# Module_I2C_GPIO.net
KiCad netlist of a schematic drawn in EAGLE
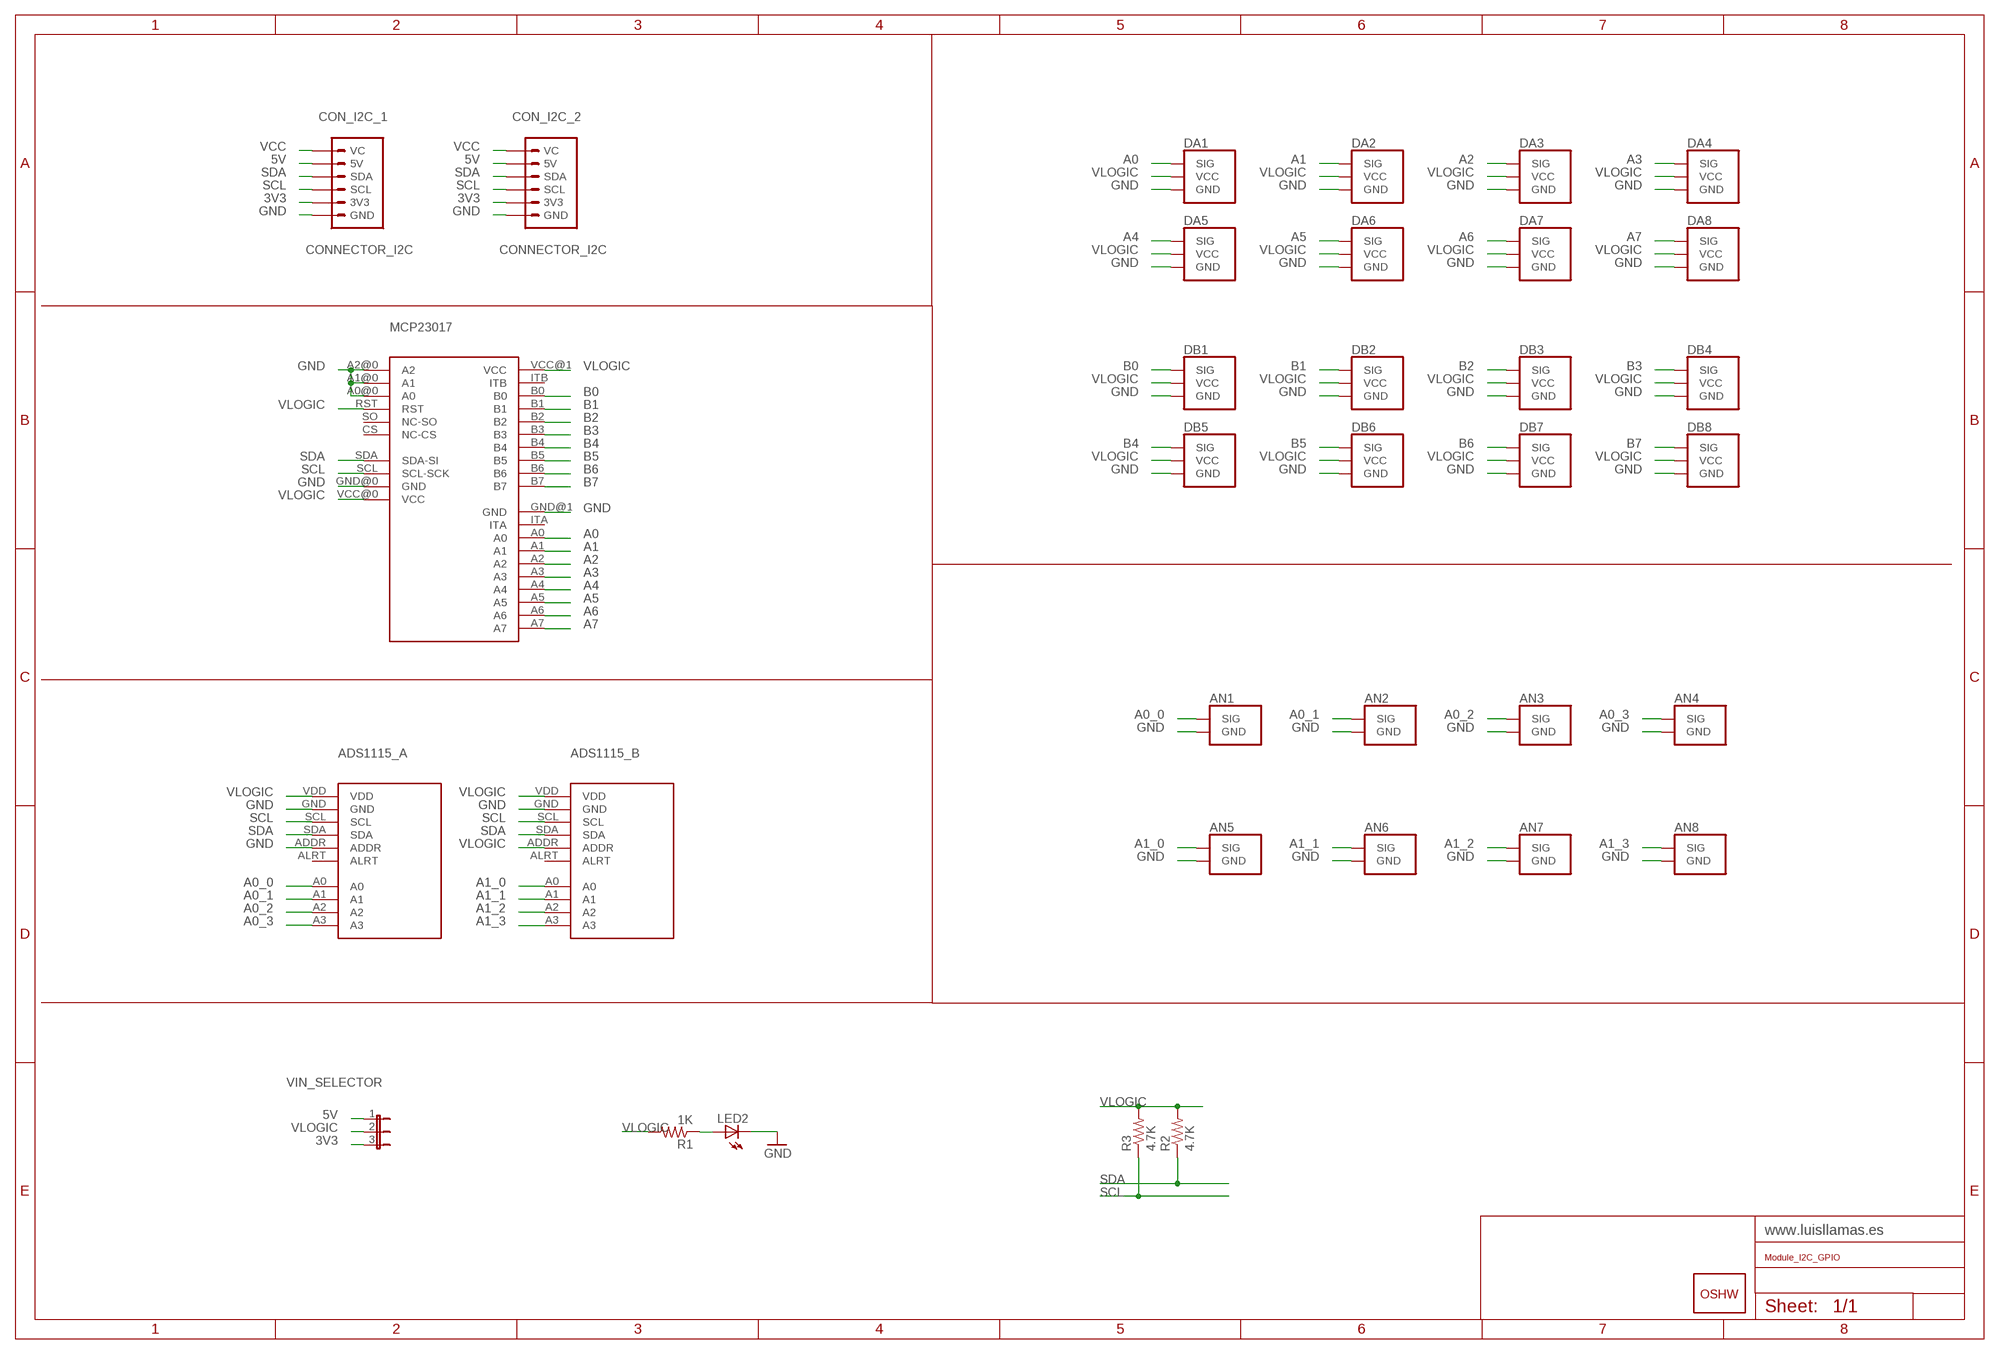
[diagram p0: schematic, sheet 1]

(export (version "E")
  (design (tool "Eeschema 10.0.6"))
  (components
    (comp (ref "ADS1115_A")
      (value "ADC-4CH-ADS1115")
      (footprint "eagle-import:ADC-4CH-ADS1115")
      (libsource (lib "eagle-import") (part "ADC-4CH-ADS1115"))
    )
    (comp (ref "ADS1115_B")
      (value "ADC-4CH-ADS1115")
      (footprint "eagle-import:ADC-4CH-ADS1115")
      (libsource (lib "eagle-import") (part "ADC-4CH-ADS1115"))
    )
    (comp (ref "AN1")
      (value "SERVO_2")
      (footprint "eagle-import:SERVO_2")
      (libsource (lib "eagle-import") (part "SERVO_2"))
    )
    (comp (ref "AN2")
      (value "SERVO_2")
      (footprint "eagle-import:SERVO_2")
      (libsource (lib "eagle-import") (part "SERVO_2"))
    )
    (comp (ref "AN3")
      (value "SERVO_2")
      (footprint "eagle-import:SERVO_2")
      (libsource (lib "eagle-import") (part "SERVO_2"))
    )
    (comp (ref "AN4")
      (value "SERVO_2")
      (footprint "eagle-import:SERVO_2")
      (libsource (lib "eagle-import") (part "SERVO_2"))
    )
    (comp (ref "AN5")
      (value "SERVO_2")
      (footprint "eagle-import:SERVO_2")
      (libsource (lib "eagle-import") (part "SERVO_2"))
    )
    (comp (ref "AN6")
      (value "SERVO_2")
      (footprint "eagle-import:SERVO_2")
      (libsource (lib "eagle-import") (part "SERVO_2"))
    )
    (comp (ref "AN7")
      (value "SERVO_2")
      (footprint "eagle-import:SERVO_2")
      (libsource (lib "eagle-import") (part "SERVO_2"))
    )
    (comp (ref "AN8")
      (value "SERVO_2")
      (footprint "eagle-import:SERVO_2")
      (libsource (lib "eagle-import") (part "SERVO_2"))
    )
    (comp (ref "CON_I2C_1")
      (value "CONNECTOR_I2C")
      (footprint "eagle-import:CONNECTOR_I2C")
      (libsource (lib "eagle-import") (part "CONNECTOR_I2C"))
    )
    (comp (ref "CON_I2C_2")
      (value "CONNECTOR_I2C")
      (footprint "eagle-import:CONNECTOR_I2C")
      (libsource (lib "eagle-import") (part "CONNECTOR_I2C"))
    )
    (comp (ref "DA1")
      (value "SERVOSERVO")
      (footprint "eagle-import:SERVO")
      (libsource (lib "eagle-import") (part "SERVOSERVO"))
    )
    (comp (ref "DA2")
      (value "SERVOSERVO")
      (footprint "eagle-import:SERVO")
      (libsource (lib "eagle-import") (part "SERVOSERVO"))
    )
    (comp (ref "DA3")
      (value "SERVOSERVO")
      (footprint "eagle-import:SERVO")
      (libsource (lib "eagle-import") (part "SERVOSERVO"))
    )
    (comp (ref "DA4")
      (value "SERVOSERVO")
      (footprint "eagle-import:SERVO")
      (libsource (lib "eagle-import") (part "SERVOSERVO"))
    )
    (comp (ref "DA5")
      (value "SERVOSERVO")
      (footprint "eagle-import:SERVO")
      (libsource (lib "eagle-import") (part "SERVOSERVO"))
    )
    (comp (ref "DA6")
      (value "SERVOSERVO")
      (footprint "eagle-import:SERVO")
      (libsource (lib "eagle-import") (part "SERVOSERVO"))
    )
    (comp (ref "DA7")
      (value "SERVOSERVO")
      (footprint "eagle-import:SERVO")
      (libsource (lib "eagle-import") (part "SERVOSERVO"))
    )
    (comp (ref "DA8")
      (value "SERVOSERVO")
      (footprint "eagle-import:SERVO")
      (libsource (lib "eagle-import") (part "SERVOSERVO"))
    )
    (comp (ref "DB1")
      (value "SERVOSERVO")
      (footprint "eagle-import:SERVO")
      (libsource (lib "eagle-import") (part "SERVOSERVO"))
    )
    (comp (ref "DB2")
      (value "SERVOSERVO")
      (footprint "eagle-import:SERVO")
      (libsource (lib "eagle-import") (part "SERVOSERVO"))
    )
    (comp (ref "DB3")
      (value "SERVOSERVO")
      (footprint "eagle-import:SERVO")
      (libsource (lib "eagle-import") (part "SERVOSERVO"))
    )
    (comp (ref "DB4")
      (value "SERVOSERVO")
      (footprint "eagle-import:SERVO")
      (libsource (lib "eagle-import") (part "SERVOSERVO"))
    )
    (comp (ref "DB5")
      (value "SERVOSERVO")
      (footprint "eagle-import:SERVO")
      (libsource (lib "eagle-import") (part "SERVOSERVO"))
    )
    (comp (ref "DB6")
      (value "SERVOSERVO")
      (footprint "eagle-import:SERVO")
      (libsource (lib "eagle-import") (part "SERVOSERVO"))
    )
    (comp (ref "DB7")
      (value "SERVOSERVO")
      (footprint "eagle-import:SERVO")
      (libsource (lib "eagle-import") (part "SERVOSERVO"))
    )
    (comp (ref "DB8")
      (value "SERVOSERVO")
      (footprint "eagle-import:SERVO")
      (libsource (lib "eagle-import") (part "SERVOSERVO"))
    )
    (comp (ref "GOLD_ORB_SM1")
      (value "OSHWLOGO_GOLD_ORB_MED")
      (footprint "eagle-import:OSHW1")
      (libsource (lib "eagle-import") (part "OSHWLOGO_GOLD_ORB_MED"))
    )
    (comp (ref "LED2")
      (value "LEDCHIP-LED0805")
      (footprint "eagle-import:CHIP-LED0805")
      (libsource (lib "eagle-import") (part "LEDCHIP-LED0805"))
    )
    (comp (ref "MCP23017")
      (value "GPIO-I2C-MCP23017")
      (footprint "eagle-import:GPIO-I2C-MCP23017")
      (libsource (lib "eagle-import") (part "GPIO-I2C-MCP23017"))
    )
    (comp (ref "R1")
      (value "1K")
      (footprint "eagle-import:R0805")
      (libsource (lib "eagle-import") (part "R-US_R0805"))
    )
    (comp (ref "R2")
      (value "4.7K")
      (footprint "eagle-import:R0805")
      (libsource (lib "eagle-import") (part "R-US_R0805"))
    )
    (comp (ref "R3")
      (value "4.7K")
      (footprint "eagle-import:R0805")
      (libsource (lib "eagle-import") (part "R-US_R0805"))
    )
    (comp (ref "VIN_SELECTOR")
      (value "JUMPER_3")
      (footprint "eagle-import:JUMPER_3")
      (libsource (lib "eagle-import") (part "JUMPER_3"))
    )
  )
  (nets
    (net (code "1") (name "/3V3") (class "Default")
      (node (ref "CON_I2C_1") (pin "3V3") (pinfunction "3V3_3V3") (pintype "passive"))
      (node (ref "CON_I2C_2") (pin "3V3") (pinfunction "3V3_3V3") (pintype "passive"))
      (node (ref "VIN_SELECTOR") (pin "3") (pinfunction "3_3") (pintype "passive"))
    )
    (net (code "2") (name "/5V") (class "Default")
      (node (ref "CON_I2C_1") (pin "5V") (pinfunction "5V_5V") (pintype "passive"))
      (node (ref "CON_I2C_2") (pin "5V") (pinfunction "5V_5V") (pintype "passive"))
      (node (ref "VIN_SELECTOR") (pin "1") (pinfunction "1_1") (pintype "passive"))
    )
    (net (code "3") (name "/A0") (class "Default")
      (node (ref "DA1") (pin "SIG") (pinfunction "SIG_SIG") (pintype "bidirectional"))
      (node (ref "MCP23017") (pin "A0") (pinfunction "A0_A0") (pintype "power_in"))
    )
    (net (code "4") (name "/A0_0") (class "Default")
      (node (ref "ADS1115_A") (pin "A0") (pinfunction "A0_A0") (pintype "input"))
      (node (ref "AN1") (pin "SIG") (pinfunction "SIG_SIG") (pintype "bidirectional"))
    )
    (net (code "5") (name "/A0_1") (class "Default")
      (node (ref "ADS1115_A") (pin "A1") (pinfunction "A1_A1") (pintype "input"))
      (node (ref "AN2") (pin "SIG") (pinfunction "SIG_SIG") (pintype "bidirectional"))
    )
    (net (code "6") (name "/A0_2") (class "Default")
      (node (ref "ADS1115_A") (pin "A2") (pinfunction "A2_A2") (pintype "input"))
      (node (ref "AN3") (pin "SIG") (pinfunction "SIG_SIG") (pintype "bidirectional"))
    )
    (net (code "7") (name "/A0_3") (class "Default")
      (node (ref "ADS1115_A") (pin "A3") (pinfunction "A3_A3") (pintype "input"))
      (node (ref "AN4") (pin "SIG") (pinfunction "SIG_SIG") (pintype "bidirectional"))
    )
    (net (code "8") (name "/A1") (class "Default")
      (node (ref "DA2") (pin "SIG") (pinfunction "SIG_SIG") (pintype "bidirectional"))
      (node (ref "MCP23017") (pin "A1") (pinfunction "A1_A1") (pintype "input"))
    )
    (net (code "9") (name "/A1_0") (class "Default")
      (node (ref "ADS1115_B") (pin "A0") (pinfunction "A0_A0") (pintype "input"))
      (node (ref "AN5") (pin "SIG") (pinfunction "SIG_SIG") (pintype "bidirectional"))
    )
    (net (code "10") (name "/A1_1") (class "Default")
      (node (ref "ADS1115_B") (pin "A1") (pinfunction "A1_A1") (pintype "input"))
      (node (ref "AN6") (pin "SIG") (pinfunction "SIG_SIG") (pintype "bidirectional"))
    )
    (net (code "11") (name "/A1_2") (class "Default")
      (node (ref "ADS1115_B") (pin "A2") (pinfunction "A2_A2") (pintype "input"))
      (node (ref "AN7") (pin "SIG") (pinfunction "SIG_SIG") (pintype "bidirectional"))
    )
    (net (code "12") (name "/A1_3") (class "Default")
      (node (ref "ADS1115_B") (pin "A3") (pinfunction "A3_A3") (pintype "input"))
      (node (ref "AN8") (pin "SIG") (pinfunction "SIG_SIG") (pintype "bidirectional"))
    )
    (net (code "13") (name "/A2") (class "Default")
      (node (ref "DA3") (pin "SIG") (pinfunction "SIG_SIG") (pintype "bidirectional"))
      (node (ref "MCP23017") (pin "A2") (pinfunction "A2_A2") (pintype "input"))
    )
    (net (code "14") (name "/A3") (class "Default")
      (node (ref "DA4") (pin "SIG") (pinfunction "SIG_SIG") (pintype "bidirectional"))
      (node (ref "MCP23017") (pin "A3") (pinfunction "A3_A3") (pintype "bidirectional"))
    )
    (net (code "15") (name "/A4") (class "Default")
      (node (ref "DA5") (pin "SIG") (pinfunction "SIG_SIG") (pintype "bidirectional"))
      (node (ref "MCP23017") (pin "A4") (pinfunction "A4_A4") (pintype "bidirectional"))
    )
    (net (code "16") (name "/A5") (class "Default")
      (node (ref "DA6") (pin "SIG") (pinfunction "SIG_SIG") (pintype "bidirectional"))
      (node (ref "MCP23017") (pin "A5") (pinfunction "A5_A5") (pintype "bidirectional"))
    )
    (net (code "17") (name "/A6") (class "Default")
      (node (ref "DA7") (pin "SIG") (pinfunction "SIG_SIG") (pintype "bidirectional"))
      (node (ref "MCP23017") (pin "A6") (pinfunction "A6_A6") (pintype "bidirectional"))
    )
    (net (code "18") (name "/A7") (class "Default")
      (node (ref "DA8") (pin "SIG") (pinfunction "SIG_SIG") (pintype "bidirectional"))
      (node (ref "MCP23017") (pin "A7") (pinfunction "A7_A7") (pintype "power_in"))
    )
    (net (code "19") (name "/B0") (class "Default")
      (node (ref "DB1") (pin "SIG") (pinfunction "SIG_SIG") (pintype "bidirectional"))
      (node (ref "MCP23017") (pin "B0") (pinfunction "B0_B0") (pintype "input"))
    )
    (net (code "20") (name "/B1") (class "Default")
      (node (ref "DB2") (pin "SIG") (pinfunction "SIG_SIG") (pintype "bidirectional"))
      (node (ref "MCP23017") (pin "B1") (pinfunction "B1_B1") (pintype "input"))
    )
    (net (code "21") (name "/B2") (class "Default")
      (node (ref "DB3") (pin "SIG") (pinfunction "SIG_SIG") (pintype "bidirectional"))
      (node (ref "MCP23017") (pin "B2") (pinfunction "B2_B2") (pintype "bidirectional"))
    )
    (net (code "22") (name "/B3") (class "Default")
      (node (ref "DB4") (pin "SIG") (pinfunction "SIG_SIG") (pintype "bidirectional"))
      (node (ref "MCP23017") (pin "B3") (pinfunction "B3_B3") (pintype "bidirectional"))
    )
    (net (code "23") (name "/B4") (class "Default")
      (node (ref "DB5") (pin "SIG") (pinfunction "SIG_SIG") (pintype "bidirectional"))
      (node (ref "MCP23017") (pin "B4") (pinfunction "B4_B4") (pintype "bidirectional"))
    )
    (net (code "24") (name "/B5") (class "Default")
      (node (ref "DB6") (pin "SIG") (pinfunction "SIG_SIG") (pintype "bidirectional"))
      (node (ref "MCP23017") (pin "B5") (pinfunction "B5_B5") (pintype "bidirectional"))
    )
    (net (code "25") (name "/B6") (class "Default")
      (node (ref "DB7") (pin "SIG") (pinfunction "SIG_SIG") (pintype "bidirectional"))
      (node (ref "MCP23017") (pin "B6") (pinfunction "B6_B6") (pintype "power_in"))
    )
    (net (code "26") (name "/B7") (class "Default")
      (node (ref "DB8") (pin "SIG") (pinfunction "SIG_SIG") (pintype "bidirectional"))
      (node (ref "MCP23017") (pin "B7") (pinfunction "B7_B7") (pintype "power_in"))
    )
    (net (code "27") (name "/SCL") (class "Default")
      (node (ref "ADS1115_A") (pin "SCL") (pinfunction "SCL_SCL") (pintype "bidirectional"))
      (node (ref "ADS1115_B") (pin "SCL") (pinfunction "SCL_SCL") (pintype "bidirectional"))
      (node (ref "CON_I2C_1") (pin "SCL") (pinfunction "SCL_SCL") (pintype "passive"))
      (node (ref "CON_I2C_2") (pin "SCL") (pinfunction "SCL_SCL") (pintype "passive"))
      (node (ref "MCP23017") (pin "SCL") (pinfunction "SCL-SCK_SCL") (pintype "input"))
      (node (ref "R3") (pin "1") (pinfunction "1_1") (pintype "passive"))
    )
    (net (code "28") (name "/SDA") (class "Default")
      (node (ref "ADS1115_A") (pin "SDA") (pinfunction "SDA_SDA") (pintype "bidirectional"))
      (node (ref "ADS1115_B") (pin "SDA") (pinfunction "SDA_SDA") (pintype "bidirectional"))
      (node (ref "CON_I2C_1") (pin "SDA") (pinfunction "SDA_SDA") (pintype "passive"))
      (node (ref "CON_I2C_2") (pin "SDA") (pinfunction "SDA_SDA") (pintype "passive"))
      (node (ref "MCP23017") (pin "SDA") (pinfunction "SDA-SI_SDA") (pintype "input"))
      (node (ref "R2") (pin "1") (pinfunction "1_1") (pintype "passive"))
    )
    (net (code "29") (name "/VCC") (class "Default")
      (node (ref "CON_I2C_1") (pin "VC") (pinfunction "VC_VC") (pintype "passive"))
      (node (ref "CON_I2C_2") (pin "VC") (pinfunction "VC_VC") (pintype "passive"))
    )
    (net (code "30") (name "/VLOGIC") (class "Default")
      (node (ref "ADS1115_A") (pin "VDD") (pinfunction "VDD_VDD") (pintype "power_in"))
      (node (ref "ADS1115_B") (pin "ADDR") (pinfunction "ADDR_ADDR") (pintype "bidirectional"))
      (node (ref "ADS1115_B") (pin "VDD") (pinfunction "VDD_VDD") (pintype "power_in"))
      (node (ref "DA1") (pin "VCC") (pinfunction "VCC_VCC") (pintype "power_in"))
      (node (ref "DA2") (pin "VCC") (pinfunction "VCC_VCC") (pintype "power_in"))
      (node (ref "DA3") (pin "VCC") (pinfunction "VCC_VCC") (pintype "power_in"))
      (node (ref "DA4") (pin "VCC") (pinfunction "VCC_VCC") (pintype "power_in"))
      (node (ref "DA5") (pin "VCC") (pinfunction "VCC_VCC") (pintype "power_in"))
      (node (ref "DA6") (pin "VCC") (pinfunction "VCC_VCC") (pintype "power_in"))
      (node (ref "DA7") (pin "VCC") (pinfunction "VCC_VCC") (pintype "power_in"))
      (node (ref "DA8") (pin "VCC") (pinfunction "VCC_VCC") (pintype "power_in"))
      (node (ref "DB1") (pin "VCC") (pinfunction "VCC_VCC") (pintype "power_in"))
      (node (ref "DB2") (pin "VCC") (pinfunction "VCC_VCC") (pintype "power_in"))
      (node (ref "DB3") (pin "VCC") (pinfunction "VCC_VCC") (pintype "power_in"))
      (node (ref "DB4") (pin "VCC") (pinfunction "VCC_VCC") (pintype "power_in"))
      (node (ref "DB5") (pin "VCC") (pinfunction "VCC_VCC") (pintype "power_in"))
      (node (ref "DB6") (pin "VCC") (pinfunction "VCC_VCC") (pintype "power_in"))
      (node (ref "DB7") (pin "VCC") (pinfunction "VCC_VCC") (pintype "power_in"))
      (node (ref "DB8") (pin "VCC") (pinfunction "VCC_VCC") (pintype "power_in"))
      (node (ref "MCP23017") (pin "RST") (pinfunction "RST_RST") (pintype "bidirectional"))
      (node (ref "MCP23017") (pin "VCC@0") (pinfunction "VCC_VCC@0") (pintype "input"))
      (node (ref "MCP23017") (pin "VCC@1") (pinfunction "VCC_VCC@1") (pintype "input"))
      (node (ref "R1") (pin "2") (pinfunction "2_2") (pintype "passive"))
      (node (ref "R2") (pin "2") (pinfunction "2_2") (pintype "passive"))
      (node (ref "R3") (pin "2") (pinfunction "2_2") (pintype "passive"))
      (node (ref "VIN_SELECTOR") (pin "2") (pinfunction "2_2") (pintype "passive"))
    )
    (net (code "31") (name "GND") (class "Default")
      (node (ref "ADS1115_A") (pin "ADDR") (pinfunction "ADDR_ADDR") (pintype "bidirectional"))
      (node (ref "ADS1115_A") (pin "GND") (pinfunction "GND_GND") (pintype "power_in"))
      (node (ref "ADS1115_B") (pin "GND") (pinfunction "GND_GND") (pintype "power_in"))
      (node (ref "AN1") (pin "GND") (pinfunction "GND_GND") (pintype "power_in"))
      (node (ref "AN2") (pin "GND") (pinfunction "GND_GND") (pintype "power_in"))
      (node (ref "AN3") (pin "GND") (pinfunction "GND_GND") (pintype "power_in"))
      (node (ref "AN4") (pin "GND") (pinfunction "GND_GND") (pintype "power_in"))
      (node (ref "AN5") (pin "GND") (pinfunction "GND_GND") (pintype "power_in"))
      (node (ref "AN6") (pin "GND") (pinfunction "GND_GND") (pintype "power_in"))
      (node (ref "AN7") (pin "GND") (pinfunction "GND_GND") (pintype "power_in"))
      (node (ref "AN8") (pin "GND") (pinfunction "GND_GND") (pintype "power_in"))
      (node (ref "CON_I2C_1") (pin "GND") (pinfunction "GND_GND") (pintype "passive"))
      (node (ref "CON_I2C_2") (pin "GND") (pinfunction "GND_GND") (pintype "passive"))
      (node (ref "DA1") (pin "GND") (pinfunction "GND_GND") (pintype "power_in"))
      (node (ref "DA2") (pin "GND") (pinfunction "GND_GND") (pintype "power_in"))
      (node (ref "DA3") (pin "GND") (pinfunction "GND_GND") (pintype "power_in"))
      (node (ref "DA4") (pin "GND") (pinfunction "GND_GND") (pintype "power_in"))
      (node (ref "DA5") (pin "GND") (pinfunction "GND_GND") (pintype "power_in"))
      (node (ref "DA6") (pin "GND") (pinfunction "GND_GND") (pintype "power_in"))
      (node (ref "DA7") (pin "GND") (pinfunction "GND_GND") (pintype "power_in"))
      (node (ref "DA8") (pin "GND") (pinfunction "GND_GND") (pintype "power_in"))
      (node (ref "DB1") (pin "GND") (pinfunction "GND_GND") (pintype "power_in"))
      (node (ref "DB2") (pin "GND") (pinfunction "GND_GND") (pintype "power_in"))
      (node (ref "DB3") (pin "GND") (pinfunction "GND_GND") (pintype "power_in"))
      (node (ref "DB4") (pin "GND") (pinfunction "GND_GND") (pintype "power_in"))
      (node (ref "DB5") (pin "GND") (pinfunction "GND_GND") (pintype "power_in"))
      (node (ref "DB6") (pin "GND") (pinfunction "GND_GND") (pintype "power_in"))
      (node (ref "DB7") (pin "GND") (pinfunction "GND_GND") (pintype "power_in"))
      (node (ref "DB8") (pin "GND") (pinfunction "GND_GND") (pintype "power_in"))
      (node (ref "LED2") (pin "C") (pinfunction "C_C") (pintype "passive"))
      (node (ref "MCP23017") (pin "A0@0") (pinfunction "A0_A0@0") (pintype "bidirectional"))
      (node (ref "MCP23017") (pin "A1@0") (pinfunction "A1_A1@0") (pintype "power_in"))
      (node (ref "MCP23017") (pin "A2@0") (pinfunction "A2_A2@0") (pintype "power_in"))
      (node (ref "MCP23017") (pin "GND@0") (pinfunction "GND_GND@0") (pintype "input"))
      (node (ref "MCP23017") (pin "GND@1") (pinfunction "GND_GND@1") (pintype "input"))
    )
    (net (code "32") (name "Net-(LED2-PadA)") (class "Default")
      (node (ref "LED2") (pin "A") (pinfunction "A_A") (pintype "passive"))
      (node (ref "R1") (pin "1") (pinfunction "1_1") (pintype "passive"))
    )
    (net (code "33") (name "unconnected-(ADS1115_A-PadALRT)") (class "Default")
      (node (ref "ADS1115_A") (pin "ALRT") (pinfunction "ALRT_ALRT") (pintype "bidirectional"))
    )
    (net (code "34") (name "unconnected-(ADS1115_B-PadALRT)") (class "Default")
      (node (ref "ADS1115_B") (pin "ALRT") (pinfunction "ALRT_ALRT") (pintype "bidirectional"))
    )
    (net (code "35") (name "unconnected-(MCP23017-NC-CS-PadCS)") (class "Default")
      (node (ref "MCP23017") (pin "CS") (pinfunction "NC-CS_CS") (pintype "bidirectional"))
    )
    (net (code "36") (name "unconnected-(MCP23017-NC-SO-PadSO)") (class "Default")
      (node (ref "MCP23017") (pin "SO") (pinfunction "NC-SO_SO") (pintype "bidirectional"))
    )
    (net (code "37") (name "unconnected-(MCP23017-PadITA)") (class "Default")
      (node (ref "MCP23017") (pin "ITA") (pinfunction "ITA_ITA") (pintype "input"))
    )
    (net (code "38") (name "unconnected-(MCP23017-PadITB)") (class "Default")
      (node (ref "MCP23017") (pin "ITB") (pinfunction "ITB_ITB") (pintype "input"))
    )
  )
)
